# myschem.net
KiCad netlist of a schematic drawn in EAGLE
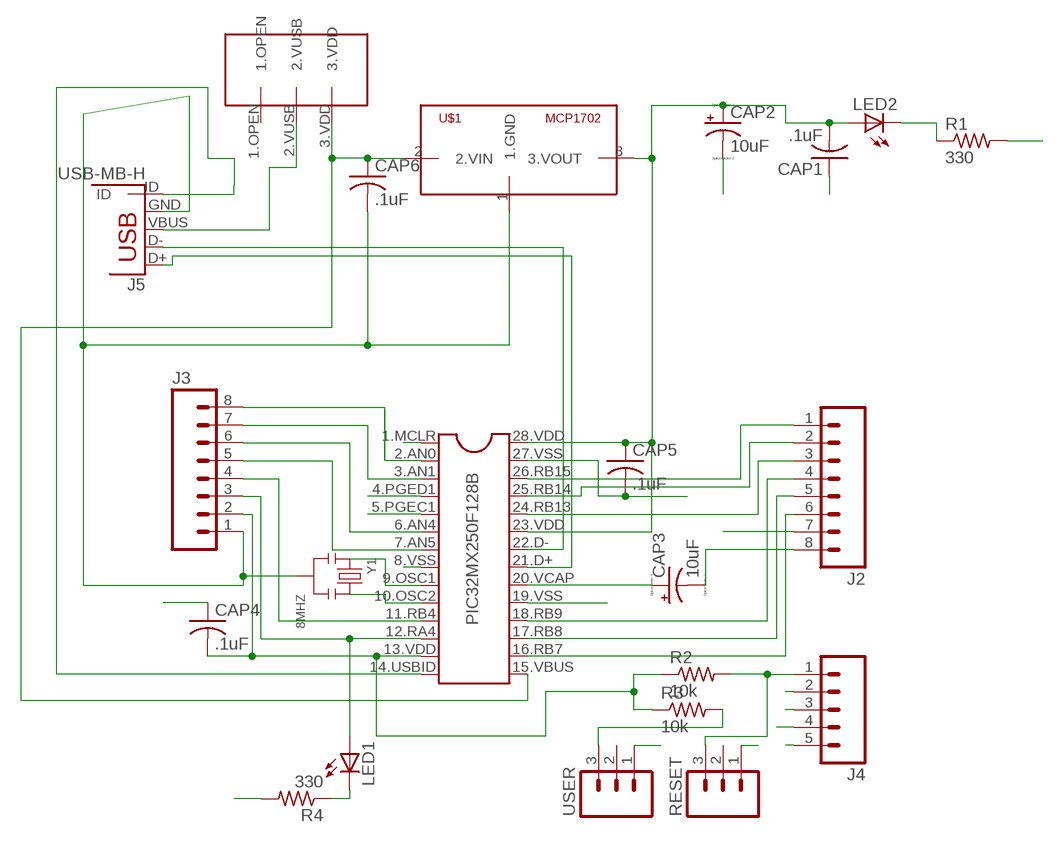
[diagram p0: schematic, sheet 1]

(export (version "E")
  (design (tool "Eeschema 10.0.6"))
  (components
    (comp (ref "CAP1")
      (value ".1uF")
      (footprint "eagle-import:C025-024X044")
      (libsource (lib "eagle-import") (part "C-US025-024X044"))
    )
    (comp (ref "CAP2")
      (value "10uF")
      (footprint "eagle-import:B45181B")
      (libsource (lib "eagle-import") (part "CPOL-USB45181B"))
    )
    (comp (ref "CAP3")
      (value "10uF")
      (footprint "eagle-import:B45181B")
      (libsource (lib "eagle-import") (part "CPOL-USB45181B"))
    )
    (comp (ref "CAP4")
      (value ".1uF")
      (footprint "eagle-import:C025-024X044")
      (libsource (lib "eagle-import") (part "C-US025-024X044"))
    )
    (comp (ref "CAP5")
      (value ".1uF")
      (footprint "eagle-import:C025-024X044")
      (libsource (lib "eagle-import") (part "C-US025-024X044"))
    )
    (comp (ref "CAP6")
      (value ".1uF")
      (footprint "eagle-import:C025-024X044")
      (libsource (lib "eagle-import") (part "C-US025-024X044"))
    )
    (comp (ref "J2")
      (value "M08")
      (footprint "eagle-import:1X08_ROUND")
      (libsource (lib "eagle-import") (part "M08"))
    )
    (comp (ref "J3")
      (value "M08")
      (footprint "eagle-import:1X08_ROUND")
      (libsource (lib "eagle-import") (part "M08"))
    )
    (comp (ref "J4")
      (value "M05PTH")
      (footprint "eagle-import:1X05")
      (libsource (lib "eagle-import") (part "M05PTH"))
    )
    (comp (ref "J5")
      (value "USB-MB-H")
      (footprint "eagle-import:USB-MB-H")
      (libsource (lib "eagle-import") (part "USB-MB-H"))
    )
    (comp (ref "LED1")
      (value "LED3MM")
      (footprint "eagle-import:LED3MM")
      (libsource (lib "eagle-import") (part "LED3MM"))
    )
    (comp (ref "LED2")
      (value "LED3MM")
      (footprint "eagle-import:LED3MM")
      (libsource (lib "eagle-import") (part "LED3MM"))
    )
    (comp (ref "PIC32MX250F128B")
      (value "DIL28-3")
      (footprint "eagle-import:DIL28-3")
      (libsource (lib "eagle-import") (part "DIL28-3"))
    )
    (comp (ref "R1")
      (value "330")
      (footprint "eagle-import:0207_10")
      (libsource (lib "eagle-import") (part "R-US_0207/10"))
    )
    (comp (ref "R2")
      (value "10k")
      (footprint "eagle-import:0207_10")
      (libsource (lib "eagle-import") (part "R-US_0207/10"))
    )
    (comp (ref "R3")
      (value "10k")
      (footprint "eagle-import:0207_10")
      (libsource (lib "eagle-import") (part "R-US_0207/10"))
    )
    (comp (ref "R4")
      (value "330")
      (footprint "eagle-import:0207_10")
      (libsource (lib "eagle-import") (part "R-US_0207/10"))
    )
    (comp (ref "RESET")
      (value "M03PTH")
      (footprint "eagle-import:1X03")
      (libsource (lib "eagle-import") (part "M03PTH"))
    )
    (comp (ref "U$1")
      (value "MCP1702")
      (footprint "eagle-import:TO92")
      (libsource (lib "eagle-import") (part "MCP1702"))
    )
    (comp (ref "U$2")
      (value "SLIDE-SWTICH")
      (footprint "eagle-import:SLIDE-SWITCH")
      (libsource (lib "eagle-import") (part "SLIDE-SWTICH"))
    )
    (comp (ref "USER")
      (value "M03PTH")
      (footprint "eagle-import:1X03")
      (libsource (lib "eagle-import") (part "M03PTH"))
    )
    (comp (ref "Y1")
      (value "8MHZ")
      (footprint "eagle-import:X3-2.5-8X3X5.5MM")
      (fields (field (name "MPN") "CSTLS8M00G53Z-A0"))
      (libsource (lib "eagle-import") (part "DIP-CERAMIC-RESONATOR/-OSCILLATOR-8MHZ(3P-2.5-8X3MM)"))
    )
  )
  (nets
    (net (code "1") (name "/GND") (class "Default")
      (node (ref "CAP1") (pin "1") (pinfunction "1_1") (pintype "passive"))
      (node (ref "CAP2") (pin "-") (pinfunction "-_-") (pintype "passive"))
      (node (ref "CAP3") (pin "-") (pinfunction "-_-") (pintype "passive"))
      (node (ref "CAP4") (pin "1") (pinfunction "1_1") (pintype "passive"))
      (node (ref "CAP5") (pin "2") (pinfunction "2_2") (pintype "passive"))
      (node (ref "CAP6") (pin "2") (pinfunction "2_2") (pintype "passive"))
      (node (ref "J2") (pin "8") (pinfunction "8_8") (pintype "passive"))
      (node (ref "J3") (pin "1") (pinfunction "1_1") (pintype "passive"))
      (node (ref "J4") (pin "3") (pinfunction "3_3") (pintype "passive"))
      (node (ref "J5") (pin "GND") (pinfunction "GND_GND") (pintype "bidirectional"))
      (node (ref "PIC32MX250F128B") (pin "19.VSS") (pinfunction "19_19.VSS") (pintype "passive"))
      (node (ref "PIC32MX250F128B") (pin "27.VSS") (pinfunction "27_27.VSS") (pintype "passive"))
      (node (ref "PIC32MX250F128B") (pin "8.VSS") (pinfunction "8_8.VSS") (pintype "passive"))
      (node (ref "R1") (pin "2") (pinfunction "2_2") (pintype "passive"))
      (node (ref "R4") (pin "2") (pinfunction "2_2") (pintype "passive"))
      (node (ref "RESET") (pin "1") (pinfunction "1_1") (pintype "passive"))
      (node (ref "U$1") (pin "1") (pinfunction "1.GND_1") (pintype "bidirectional"))
      (node (ref "USER") (pin "1") (pinfunction "1_1") (pintype "passive"))
      (node (ref "Y1") (pin "2") (pinfunction "2_2") (pintype "passive"))
    )
    (net (code "2") (name "/MCLR") (class "Default")
      (node (ref "J4") (pin "1") (pinfunction "1_1") (pintype "passive"))
      (node (ref "PIC32MX250F128B") (pin "1.MCLR") (pinfunction "1_1.MCLR") (pintype "passive"))
      (node (ref "R2") (pin "2") (pinfunction "2_2") (pintype "passive"))
      (node (ref "RESET") (pin "3") (pinfunction "3_3") (pintype "passive"))
    )
    (net (code "3") (name "/PGEC1") (class "Default")
      (node (ref "J4") (pin "5") (pinfunction "5_5") (pintype "passive"))
      (node (ref "PIC32MX250F128B") (pin "5.PGEC1") (pinfunction "5_5.PGEC1") (pintype "passive"))
    )
    (net (code "4") (name "/PGED1") (class "Default")
      (node (ref "J4") (pin "4") (pinfunction "4_4") (pintype "passive"))
      (node (ref "PIC32MX250F128B") (pin "4.PGED1") (pinfunction "4_4.PGED1") (pintype "passive"))
    )
    (net (code "5") (name "/USER") (class "Default")
      (node (ref "J3") (pin "4") (pinfunction "4_4") (pintype "passive"))
      (node (ref "PIC32MX250F128B") (pin "11.RB4") (pinfunction "11_11.RB4") (pintype "passive"))
      (node (ref "R3") (pin "2") (pinfunction "2_2") (pintype "passive"))
      (node (ref "USER") (pin "3") (pinfunction "3_3") (pintype "passive"))
    )
    (net (code "6") (name "/VBUS") (class "Default")
      (node (ref "CAP6") (pin "1") (pinfunction "1_1") (pintype "passive"))
      (node (ref "J2") (pin "7") (pinfunction "7_7") (pintype "passive"))
      (node (ref "PIC32MX250F128B") (pin "15.VBUS") (pinfunction "15_15.VBUS") (pintype "passive"))
      (node (ref "U$1") (pin "2") (pinfunction "2.VIN_2") (pintype "bidirectional"))
      (node (ref "U$2") (pin "3.VDD") (pinfunction "3.VDD_3.VDD") (pintype "bidirectional"))
    )
    (net (code "7") (name "/VDD") (class "Default")
      (node (ref "CAP1") (pin "2") (pinfunction "2_2") (pintype "passive"))
      (node (ref "CAP2") (pin "+") (pinfunction "+_+") (pintype "passive"))
      (node (ref "CAP4") (pin "2") (pinfunction "2_2") (pintype "passive"))
      (node (ref "CAP5") (pin "1") (pinfunction "1_1") (pintype "passive"))
      (node (ref "J3") (pin "2") (pinfunction "2_2") (pintype "passive"))
      (node (ref "J4") (pin "2") (pinfunction "2_2") (pintype "passive"))
      (node (ref "LED2") (pin "A") (pinfunction "A_A") (pintype "passive"))
      (node (ref "PIC32MX250F128B") (pin "13.VDD") (pinfunction "13_13.VDD") (pintype "passive"))
      (node (ref "PIC32MX250F128B") (pin "23.VDD") (pinfunction "23_23.VDD") (pintype "passive"))
      (node (ref "PIC32MX250F128B") (pin "28.VDD") (pinfunction "28_28.VDD") (pintype "passive"))
      (node (ref "R2") (pin "1") (pinfunction "1_1") (pintype "passive"))
      (node (ref "R3") (pin "1") (pinfunction "1_1") (pintype "passive"))
      (node (ref "U$1") (pin "3") (pinfunction "3.VOUT_3") (pintype "bidirectional"))
    )
    (net (code "8") (name "Net-(J5-PadVBUS)") (class "Default")
      (node (ref "J5") (pin "VBUS") (pinfunction "VBUS_VBUS") (pintype "bidirectional"))
      (node (ref "U$2") (pin "2.VUSB") (pinfunction "2.VUSB_2.VUSB") (pintype "bidirectional"))
    )
    (net (code "9") (name "Net-(LED1-C)") (class "Default")
      (node (ref "LED1") (pin "K") (pinfunction "C_K") (pintype "passive"))
      (node (ref "R4") (pin "1") (pinfunction "1_1") (pintype "passive"))
    )
    (net (code "10") (name "Net-(LED2-C)") (class "Default")
      (node (ref "LED2") (pin "K") (pinfunction "C_K") (pintype "passive"))
      (node (ref "R1") (pin "1") (pinfunction "1_1") (pintype "passive"))
    )
    (net (code "11") (name "Net-(PIC32MX250F128B-2)") (class "Default")
      (node (ref "J3") (pin "8") (pinfunction "8_8") (pintype "passive"))
      (node (ref "PIC32MX250F128B") (pin "2.AN0") (pinfunction "2_2.AN0") (pintype "passive"))
    )
    (net (code "12") (name "Net-(PIC32MX250F128B-3)") (class "Default")
      (node (ref "J3") (pin "7") (pinfunction "7_7") (pintype "passive"))
      (node (ref "PIC32MX250F128B") (pin "3.AN1") (pinfunction "3_3.AN1") (pintype "passive"))
    )
    (net (code "13") (name "Net-(PIC32MX250F128B-6)") (class "Default")
      (node (ref "J3") (pin "6") (pinfunction "6_6") (pintype "passive"))
      (node (ref "PIC32MX250F128B") (pin "6.AN4") (pinfunction "6_6.AN4") (pintype "passive"))
    )
    (net (code "14") (name "Net-(PIC32MX250F128B-7)") (class "Default")
      (node (ref "J3") (pin "5") (pinfunction "5_5") (pintype "passive"))
      (node (ref "PIC32MX250F128B") (pin "7.AN5") (pinfunction "7_7.AN5") (pintype "passive"))
    )
    (net (code "15") (name "Net-(PIC32MX250F128B-9)") (class "Default")
      (node (ref "PIC32MX250F128B") (pin "9.OSC1") (pinfunction "9_9.OSC1") (pintype "passive"))
      (node (ref "Y1") (pin "1") (pinfunction "1_1") (pintype "passive"))
    )
    (net (code "16") (name "Net-(PIC32MX250F128B-10)") (class "Default")
      (node (ref "PIC32MX250F128B") (pin "10.OSC2") (pinfunction "10_10.OSC2") (pintype "passive"))
      (node (ref "Y1") (pin "3") (pinfunction "3_3") (pintype "passive"))
    )
    (net (code "17") (name "Net-(PIC32MX250F128B-12)") (class "Default")
      (node (ref "J3") (pin "3") (pinfunction "3_3") (pintype "passive"))
      (node (ref "LED1") (pin "A") (pinfunction "A_A") (pintype "passive"))
      (node (ref "PIC32MX250F128B") (pin "12.RA4") (pinfunction "12_12.RA4") (pintype "passive"))
    )
    (net (code "18") (name "Net-(PIC32MX250F128B-14)") (class "Default")
      (node (ref "J5") (pin "ID") (pinfunction "ID_ID") (pintype "bidirectional"))
      (node (ref "PIC32MX250F128B") (pin "14.USBID") (pinfunction "14_14.USBID") (pintype "passive"))
    )
    (net (code "19") (name "Net-(PIC32MX250F128B-16)") (class "Default")
      (node (ref "J2") (pin "6") (pinfunction "6_6") (pintype "passive"))
      (node (ref "PIC32MX250F128B") (pin "16.RB7") (pinfunction "16_16.RB7") (pintype "passive"))
    )
    (net (code "20") (name "Net-(PIC32MX250F128B-17)") (class "Default")
      (node (ref "J2") (pin "5") (pinfunction "5_5") (pintype "passive"))
      (node (ref "PIC32MX250F128B") (pin "17.RB8") (pinfunction "17_17.RB8") (pintype "passive"))
    )
    (net (code "21") (name "Net-(PIC32MX250F128B-18)") (class "Default")
      (node (ref "J2") (pin "4") (pinfunction "4_4") (pintype "passive"))
      (node (ref "PIC32MX250F128B") (pin "18.RB9") (pinfunction "18_18.RB9") (pintype "passive"))
    )
    (net (code "22") (name "Net-(PIC32MX250F128B-20)") (class "Default")
      (node (ref "CAP3") (pin "+") (pinfunction "+_+") (pintype "passive"))
      (node (ref "PIC32MX250F128B") (pin "20.VCAP") (pinfunction "20_20.VCAP") (pintype "passive"))
    )
    (net (code "23") (name "Net-(PIC32MX250F128B-21)") (class "Default")
      (node (ref "J5") (pin "D+") (pinfunction "D+_D+") (pintype "bidirectional"))
      (node (ref "PIC32MX250F128B") (pin "21.D+") (pinfunction "21_21.D+") (pintype "passive"))
    )
    (net (code "24") (name "Net-(PIC32MX250F128B-22)") (class "Default")
      (node (ref "J5") (pin "D-") (pinfunction "D-_D-") (pintype "bidirectional"))
      (node (ref "PIC32MX250F128B") (pin "22.D-") (pinfunction "22_22.D-") (pintype "passive"))
    )
    (net (code "25") (name "Net-(PIC32MX250F128B-24)") (class "Default")
      (node (ref "J2") (pin "3") (pinfunction "3_3") (pintype "passive"))
      (node (ref "PIC32MX250F128B") (pin "24.RB13") (pinfunction "24_24.RB13") (pintype "passive"))
    )
    (net (code "26") (name "Net-(PIC32MX250F128B-25)") (class "Default")
      (node (ref "J2") (pin "2") (pinfunction "2_2") (pintype "passive"))
      (node (ref "PIC32MX250F128B") (pin "25.RB14") (pinfunction "25_25.RB14") (pintype "passive"))
    )
    (net (code "27") (name "Net-(PIC32MX250F128B-26)") (class "Default")
      (node (ref "J2") (pin "1") (pinfunction "1_1") (pintype "passive"))
      (node (ref "PIC32MX250F128B") (pin "26.RB15") (pinfunction "26_26.RB15") (pintype "passive"))
    )
    (net (code "28") (name "unconnected-(RESET-Pad2)") (class "Default")
      (node (ref "RESET") (pin "2") (pinfunction "2_2") (pintype "passive"))
    )
    (net (code "29") (name "unconnected-(U$2-Pad1.OPEN)") (class "Default")
      (node (ref "U$2") (pin "1.OPEN") (pinfunction "1.OPEN_1.OPEN") (pintype "bidirectional"))
    )
    (net (code "30") (name "unconnected-(USER-Pad2)") (class "Default")
      (node (ref "USER") (pin "2") (pinfunction "2_2") (pintype "passive"))
    )
  )
)
